# IMU.net
KiCad netlist of a schematic drawn in Altium Designer
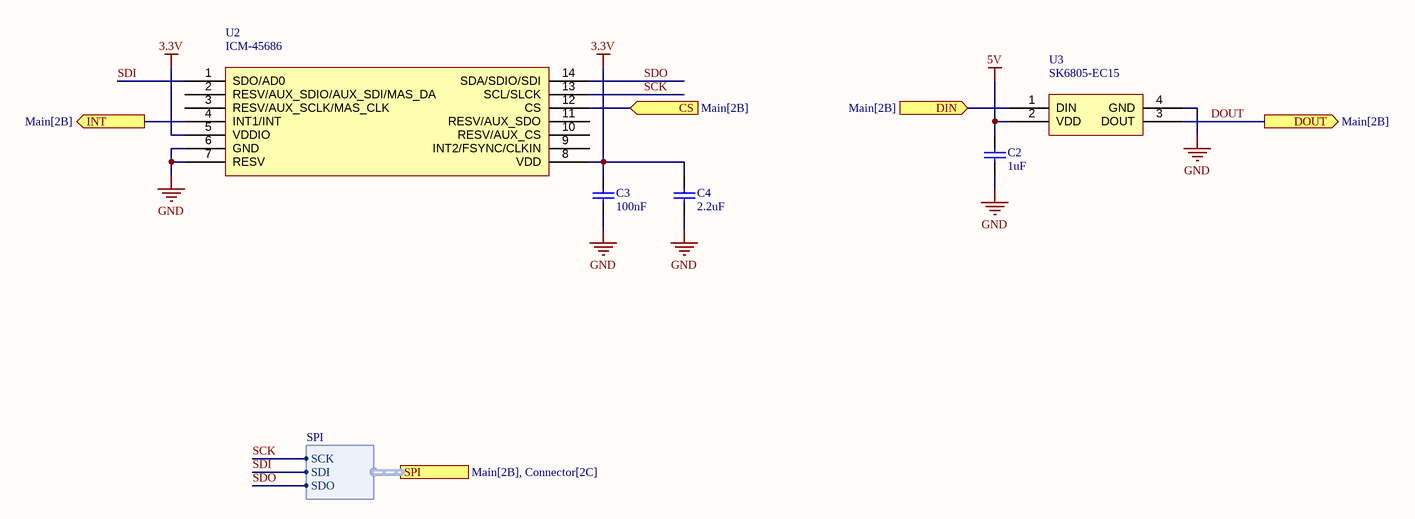
[diagram p0: IMU.SchDoc]

(export (version "E")
  (design (tool "Eeschema 10.0.6"))
  (components
    (comp (ref "C2") (value "1uF") (footprint "Capacitor 0201") (libsource (lib "x-io") (part "Capacitor")))
    (comp (ref "C3") (value "100nF") (footprint "Capacitor 0201") (libsource (lib "x-io") (part "Capacitor")))
    (comp (ref "C4") (value "2.2uF") (footprint "Capacitor 0201") (libsource (lib "x-io") (part "Capacitor")))
    (comp (ref "U2") (value "ICM-45686") (footprint "ICM-45686") (libsource (lib "x-io") (part "ICM-45686")))
    (comp (ref "U3")
      (value "SK6805-EC15")
      (footprint "SK6805-EC15")
      (libsource (lib "x-io") (part "SK6805-EC15"))
    )
  )
  (nets
    (net (code "2") (name "/CS") (class "Default")
      (node (ref "U2") (pin "12") (pinfunction "CS_12") (pintype "passive"))
    )
    (net (code "3") (name "/DIN") (class "Default")
      (node (ref "U3") (pin "1") (pinfunction "DIN_1") (pintype "passive"))
    )
    (net (code "4") (name "/DOUT") (class "Default")
      (node (ref "U3") (pin "3") (pinfunction "DOUT_3") (pintype "passive"))
    )
    (net (code "5") (name "/INT") (class "Default")
      (node (ref "U2") (pin "4") (pinfunction "INT1/INT_4") (pintype "passive"))
    )
    (net (code "6") (name "/SCK") (class "Default")
      (node (ref "U2") (pin "13") (pinfunction "SCL/SLCK_13") (pintype "passive"))
    )
    (net (code "7") (name "/SDI") (class "Default")
      (node (ref "U2") (pin "1") (pinfunction "SDO/AD0_1") (pintype "passive"))
    )
    (net (code "8") (name "/SDO") (class "Default")
      (node (ref "U2") (pin "14") (pinfunction "SDA/SDIO/SDI_14") (pintype "passive"))
    )
    (net (code "10") (name "3.3V") (class "Default")
      (node (ref "C3") (pin "2") (pinfunction "2_2") (pintype "passive"))
      (node (ref "C4") (pin "2") (pinfunction "2_2") (pintype "passive"))
      (node (ref "U2") (pin "5") (pinfunction "VDDIO_5") (pintype "passive"))
      (node (ref "U2") (pin "8") (pinfunction "VDD_8") (pintype "passive"))
    )
    (net (code "11") (name "5V") (class "Default")
      (node (ref "C2") (pin "2") (pinfunction "2_2") (pintype "passive"))
      (node (ref "U3") (pin "2") (pinfunction "VDD_2") (pintype "passive"))
    )
    (net (code "12") (name "GND") (class "Default")
      (node (ref "C2") (pin "1") (pinfunction "1_1") (pintype "passive"))
      (node (ref "C3") (pin "1") (pinfunction "1_1") (pintype "passive"))
      (node (ref "C4") (pin "1") (pinfunction "1_1") (pintype "passive"))
      (node (ref "U2") (pin "6") (pinfunction "GND_6") (pintype "passive"))
      (node (ref "U2") (pin "7") (pinfunction "RESV_7") (pintype "passive"))
      (node (ref "U3") (pin "4") (pinfunction "GND_4") (pintype "passive"))
    )
    (net (code "13") (name "unconnected-(U2-INT2{slash}FSYNC{slash}CLKIN-Pad9)") (class "Default")
      (node (ref "U2") (pin "9") (pinfunction "INT2/FSYNC/CLKIN_9") (pintype "passive"))
    )
    (net (code "14") (name "unconnected-(U2-RESV{slash}AUX_CS-Pad10)") (class "Default")
      (node (ref "U2") (pin "10") (pinfunction "RESV/AUX_CS_10") (pintype "passive"))
    )
    (net (code "15") (name "unconnected-(U2-RESV{slash}AUX_SCLK{slash}MAS_CLK-Pad3)") (class "Default")
      (node (ref "U2") (pin "3") (pinfunction "RESV/AUX_SCLK/MAS_CLK_3") (pintype "passive"))
    )
    (net (code "16") (name "unconnected-(U2-RESV{slash}AUX_SDIO{slash}AUX_SDI{slash}MAS_DA-Pad2)") (class "Default")
      (node (ref "U2") (pin "2") (pinfunction "RESV/AUX_SDIO/AUX_SDI/MAS_DA_2") (pintype "passive"))
    )
    (net (code "17") (name "unconnected-(U2-RESV{slash}AUX_SDO-Pad11)") (class "Default")
      (node (ref "U2") (pin "11") (pinfunction "RESV/AUX_SDO_11") (pintype "passive"))
    )
  )
)
